# Top.net
KiCad netlist of a schematic drawn in Altium Designer
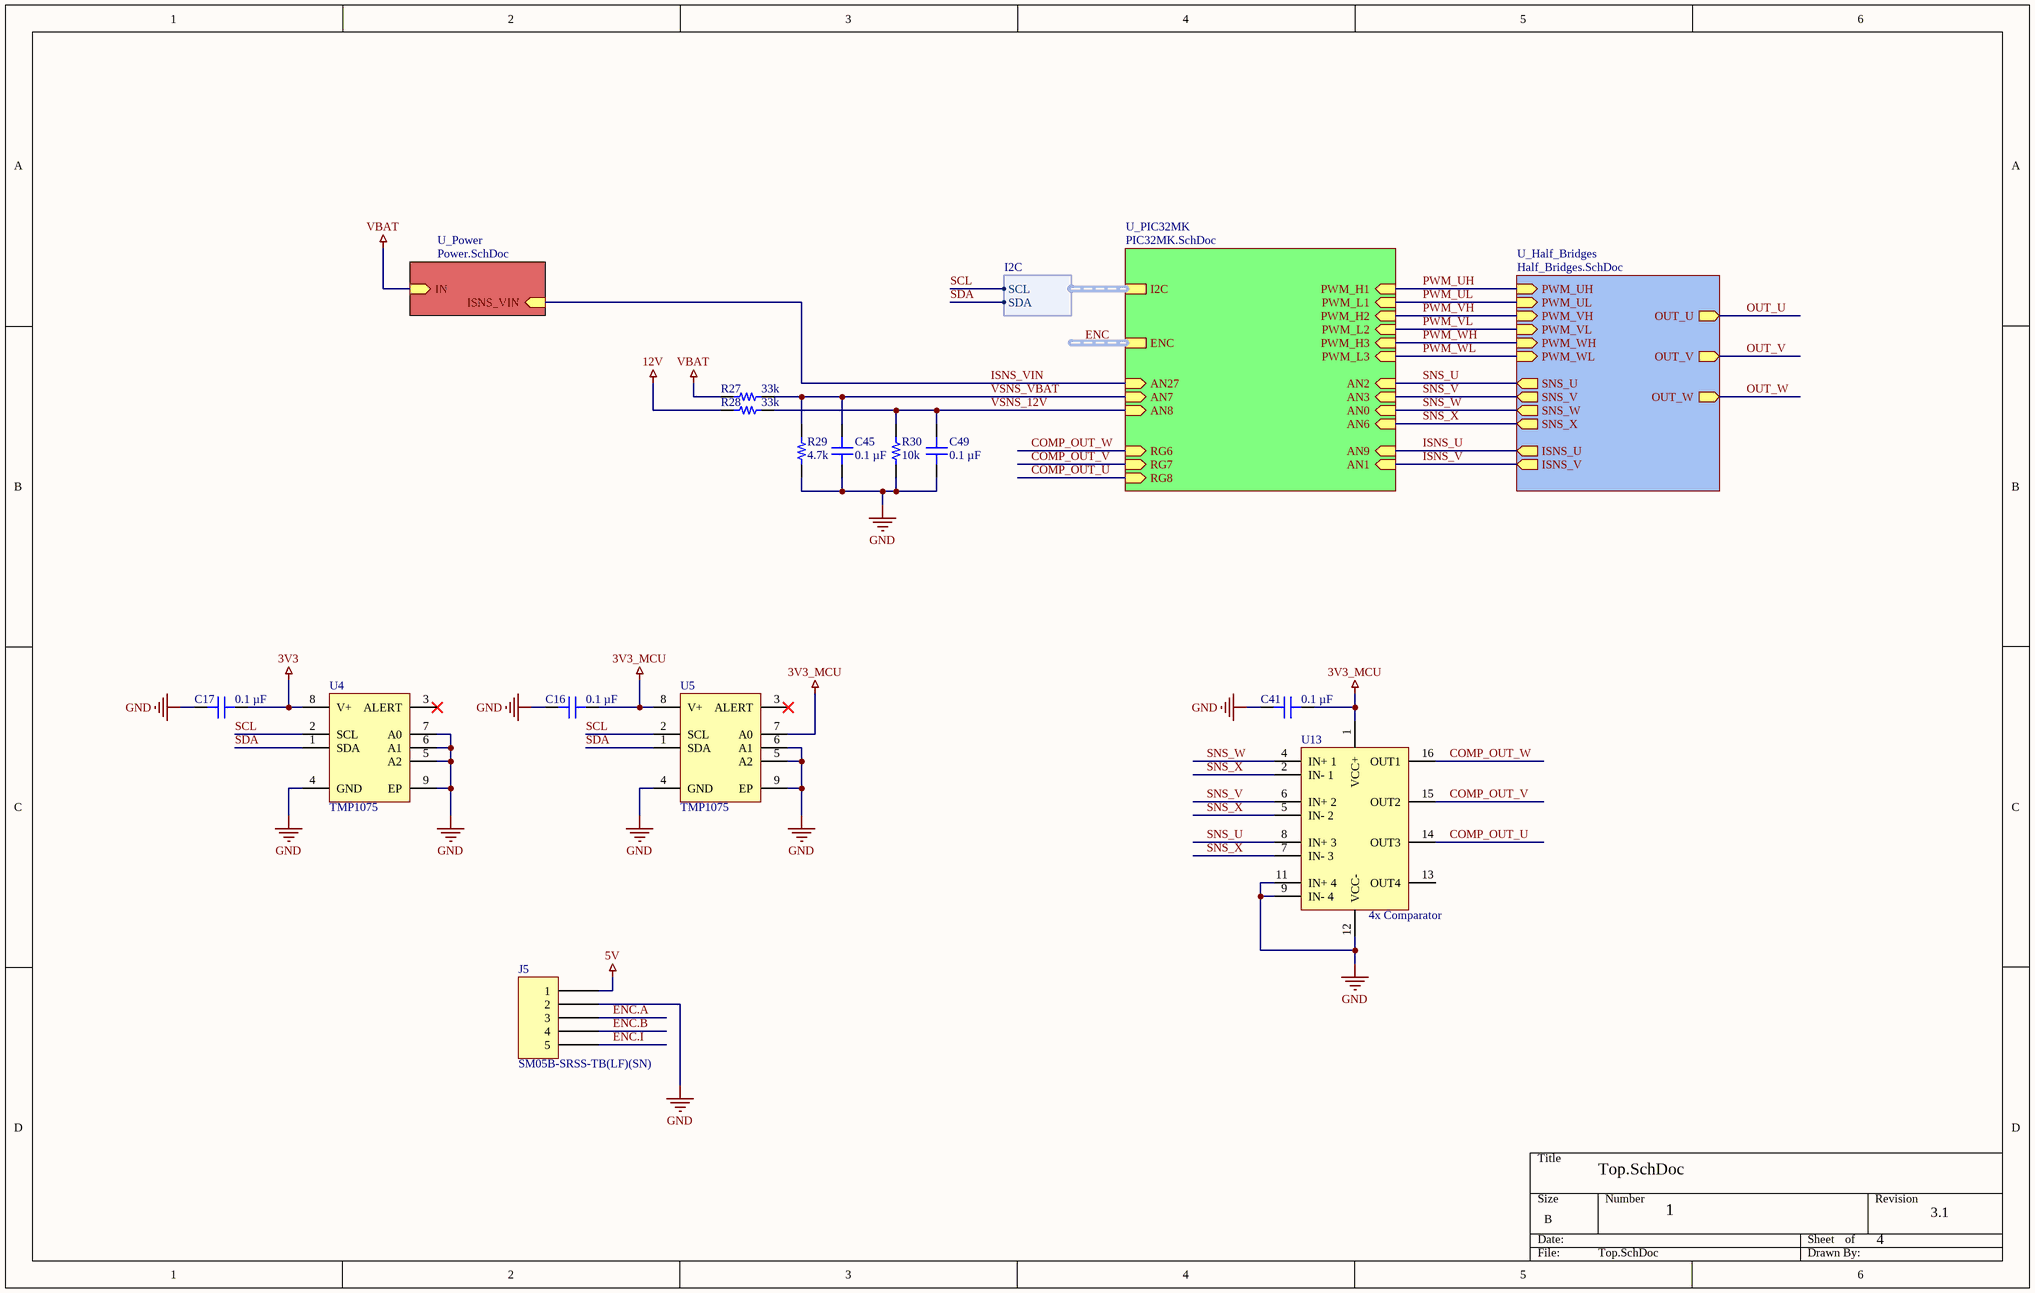
[diagram p0: Top.SchDoc]

(export (version "E")
  (design (tool "Eeschema 10.0.6"))
  (components
    (comp (ref "C16")
      (value "0.1 µF")
      (footprint "CAP 0402_1005")
      (description "CAP CER 0.1UF 16V X7R 0402")
      (fields (field (name "PART NUMBER") "C0402C104K4RACAUTO") (field (name "MANUFACTURER") "KEMET"))
      (libsource (lib "Celestial Altium Library - altium_library") (part "Capacitor"))
    )
    (comp (ref "C17")
      (value "0.1 µF")
      (footprint "CAP 0402_1005")
      (description "CAP CER 0.1UF 16V X7R 0402")
      (fields (field (name "PART NUMBER") "C0402C104K4RACAUTO") (field (name "MANUFACTURER") "KEMET"))
      (libsource (lib "Celestial Altium Library - altium_library") (part "Capacitor"))
    )
    (comp (ref "C41")
      (value "0.1 µF")
      (footprint "CAP 0402_1005")
      (description "CAP CER 0.1UF 16V X7R 0402")
      (fields (field (name "PART NUMBER") "C0402C104K4RACAUTO") (field (name "MANUFACTURER") "KEMET"))
      (libsource (lib "Celestial Altium Library - altium_library") (part "Capacitor"))
    )
    (comp (ref "C45")
      (value "0.1 µF")
      (footprint "CAP 0402_1005")
      (description "CAP CER 0.1UF 16V X7R 0402")
      (fields (field (name "PART NUMBER") "C0402C104K4RACAUTO") (field (name "MANUFACTURER") "KEMET"))
      (libsource (lib "Celestial Altium Library - altium_library") (part "Capacitor"))
    )
    (comp (ref "C49")
      (value "0.1 µF")
      (footprint "CAP 0402_1005")
      (description "CAP CER 0.1UF 16V X7R 0402")
      (fields (field (name "PART NUMBER") "C0402C104K4RACAUTO") (field (name "MANUFACTURER") "KEMET"))
      (libsource (lib "Celestial Altium Library - altium_library") (part "Capacitor"))
    )
    (comp (ref "J5")
      (value "SM05B-SRSS-TB(LF)(SN)")
      (footprint "JST SM05B-SRSS-TB")
      (description "CONN HEADER SMD R/A 5POS 1MM")
      (fields (field (name "MANUFACTURER") "JST Sales America Inc."))
      (libsource (lib "Celestial Altium Library - altium_library") (part "5 Pin"))
    )
    (comp (ref "R27")
      (value "33k")
      (footprint "RES 0402_1005")
      (description "RES 14.3K OHM 1% 1/10W 0402")
      (fields
        (field (name "PART NUMBER") "RK73H1ETTP1432F")
        (field (name "MANUFACTURER") "KOA Speer Electronics, Inc.")
      )
      (libsource (lib "Celestial Altium Library - altium_library") (part "Resistor"))
    )
    (comp (ref "R28")
      (value "33k")
      (footprint "RES 0402_1005")
      (description "RES 14.3K OHM 1% 1/10W 0402")
      (fields
        (field (name "PART NUMBER") "RK73H1ETTP1432F")
        (field (name "MANUFACTURER") "KOA Speer Electronics, Inc.")
      )
      (libsource (lib "Celestial Altium Library - altium_library") (part "Resistor"))
    )
    (comp (ref "R29")
      (value "4.7k")
      (footprint "RES 0402_1005")
      (description "RES 14.3K OHM 1% 1/10W 0402")
      (fields
        (field (name "PART NUMBER") "RK73H1ETTP1432F")
        (field (name "MANUFACTURER") "KOA Speer Electronics, Inc.")
      )
      (libsource (lib "Celestial Altium Library - altium_library") (part "Resistor"))
    )
    (comp (ref "R30")
      (value "10k")
      (footprint "RES 0402_1005")
      (description "RES 14.3K OHM 1% 1/10W 0402")
      (fields
        (field (name "PART NUMBER") "RK73H1ETTP1432F")
        (field (name "MANUFACTURER") "KOA Speer Electronics, Inc.")
      )
      (libsource (lib "Celestial Altium Library - altium_library") (part "Resistor"))
    )
    (comp (ref "U4")
      (value "TMP1075")
      (footprint "8_WSON_2x2_0.5mm")
      (description "I2C TEMP SENSOR")
      (libsource (lib "IC") (part "TMP1075"))
    )
    (comp (ref "U5")
      (value "TMP1075")
      (footprint "8_WSON_2x2_0.5mm")
      (description "I2C TEMP SENSOR")
      (libsource (lib "IC") (part "TMP1075"))
    )
    (comp (ref "U13")
      (value "4x Comparator")
      (footprint "QFN50P300X300X100-16N")
      (description "Comparator General Purpose CMOS, DTL, MOS, Open-Collector, TTL 16-QFN (3x3)")
      (libsource (lib "IC") (part "LM2901Q4T"))
    )
  )
  (nets
    (net (code "3") (name "/COMP_OUT_U") (class "Default")
      (node (ref "U13") (pin "14") (pinfunction "OUT3_14") (pintype "passive"))
    )
    (net (code "4") (name "/COMP_OUT_V") (class "Default")
      (node (ref "U13") (pin "15") (pinfunction "OUT2_15") (pintype "passive"))
    )
    (net (code "5") (name "/COMP_OUT_W") (class "Default")
      (node (ref "U13") (pin "16") (pinfunction "OUT1_16") (pintype "passive"))
    )
    (net (code "6") (name "/ENC.A") (class "Default")
      (node (ref "J5") (pin "3") (pinfunction "3_3") (pintype "passive"))
    )
    (net (code "7") (name "/ENC.B") (class "Default")
      (node (ref "J5") (pin "4") (pinfunction "4_4") (pintype "passive"))
    )
    (net (code "8") (name "/ENC.I") (class "Default")
      (node (ref "J5") (pin "5") (pinfunction "5_5") (pintype "passive"))
    )
    (net (code "21") (name "/SCL") (class "Default")
      (node (ref "U4") (pin "2") (pinfunction "SCL_2") (pintype "passive"))
      (node (ref "U5") (pin "2") (pinfunction "SCL_2") (pintype "passive"))
    )
    (net (code "22") (name "/SDA") (class "Default")
      (node (ref "U4") (pin "1") (pinfunction "SDA_1") (pintype "passive"))
      (node (ref "U5") (pin "1") (pinfunction "SDA_1") (pintype "passive"))
    )
    (net (code "23") (name "/SNS_U") (class "Default")
      (node (ref "U13") (pin "8") (pinfunction "IN+_3_8") (pintype "passive"))
    )
    (net (code "24") (name "/SNS_V") (class "Default")
      (node (ref "U13") (pin "6") (pinfunction "IN+_2_6") (pintype "passive"))
    )
    (net (code "25") (name "/SNS_W") (class "Default")
      (node (ref "U13") (pin "4") (pinfunction "IN+_1_4") (pintype "passive"))
    )
    (net (code "26") (name "/SNS_X") (class "Default")
      (node (ref "U13") (pin "2") (pinfunction "IN-_1_2") (pintype "passive"))
      (node (ref "U13") (pin "5") (pinfunction "IN-_2_5") (pintype "passive"))
      (node (ref "U13") (pin "7") (pinfunction "IN-_3_7") (pintype "passive"))
    )
    (net (code "27") (name "/VSNS_12V") (class "Default")
      (node (ref "C49") (pin "2") (pinfunction "2_2") (pintype "passive"))
      (node (ref "R28") (pin "1") (pinfunction "1_1") (pintype "passive"))
      (node (ref "R30") (pin "1") (pinfunction "1_1") (pintype "passive"))
    )
    (net (code "28") (name "/VSNS_VBAT") (class "Default")
      (node (ref "C45") (pin "2") (pinfunction "2_2") (pintype "passive"))
      (node (ref "R27") (pin "1") (pinfunction "1_1") (pintype "passive"))
      (node (ref "R29") (pin "1") (pinfunction "1_1") (pintype "passive"))
    )
    (net (code "31") (name "3V3") (class "Default")
      (node (ref "C17") (pin "2") (pinfunction "2_2") (pintype "passive"))
      (node (ref "U4") (pin "8") (pinfunction "V+_8") (pintype "passive"))
    )
    (net (code "32") (name "3V3_MCU") (class "Default")
      (node (ref "C16") (pin "2") (pinfunction "2_2") (pintype "passive"))
      (node (ref "C41") (pin "2") (pinfunction "2_2") (pintype "passive"))
      (node (ref "U13") (pin "1") (pinfunction "VCC+_1") (pintype "passive"))
      (node (ref "U5") (pin "7") (pinfunction "A0_7") (pintype "passive"))
      (node (ref "U5") (pin "8") (pinfunction "V+_8") (pintype "passive"))
    )
    (net (code "33") (name "5V") (class "Default")
      (node (ref "J5") (pin "1") (pinfunction "1_1") (pintype "passive"))
    )
    (net (code "34") (name "12V") (class "Default")
      (node (ref "R28") (pin "2") (pinfunction "2_2") (pintype "passive"))
    )
    (net (code "35") (name "GND") (class "Default")
      (node (ref "C16") (pin "1") (pinfunction "1_1") (pintype "passive"))
      (node (ref "C17") (pin "1") (pinfunction "1_1") (pintype "passive"))
      (node (ref "C41") (pin "1") (pinfunction "1_1") (pintype "passive"))
      (node (ref "C45") (pin "1") (pinfunction "1_1") (pintype "passive"))
      (node (ref "C49") (pin "1") (pinfunction "1_1") (pintype "passive"))
      (node (ref "J5") (pin "2") (pinfunction "2_2") (pintype "passive"))
      (node (ref "R29") (pin "2") (pinfunction "2_2") (pintype "passive"))
      (node (ref "R30") (pin "2") (pinfunction "2_2") (pintype "passive"))
      (node (ref "U13") (pin "11") (pinfunction "IN+_4_11") (pintype "passive"))
      (node (ref "U13") (pin "12") (pinfunction "VCC-_12") (pintype "passive"))
      (node (ref "U13") (pin "9") (pinfunction "IN-_4_9") (pintype "passive"))
      (node (ref "U4") (pin "4") (pinfunction "GND_4") (pintype "passive"))
      (node (ref "U4") (pin "5") (pinfunction "A2_5") (pintype "passive"))
      (node (ref "U4") (pin "6") (pinfunction "A1_6") (pintype "passive"))
      (node (ref "U4") (pin "7") (pinfunction "A0_7") (pintype "passive"))
      (node (ref "U4") (pin "9") (pinfunction "EP_9") (pintype "passive"))
      (node (ref "U5") (pin "4") (pinfunction "GND_4") (pintype "passive"))
      (node (ref "U5") (pin "5") (pinfunction "A2_5") (pintype "passive"))
      (node (ref "U5") (pin "6") (pinfunction "A1_6") (pintype "passive"))
      (node (ref "U5") (pin "9") (pinfunction "EP_9") (pintype "passive"))
    )
    (net (code "36") (name "VBAT") (class "Default")
      (node (ref "R27") (pin "2") (pinfunction "2_2") (pintype "passive"))
    )
    (net (code "37") (name "unconnected-(U4-ALERT-Pad3)") (class "Default")
      (node (ref "U4") (pin "3") (pinfunction "ALERT_3") (pintype "passive+no_connect"))
    )
    (net (code "38") (name "unconnected-(U5-ALERT-Pad3)") (class "Default")
      (node (ref "U5") (pin "3") (pinfunction "ALERT_3") (pintype "passive+no_connect"))
    )
    (net (code "39") (name "unconnected-(U13-OUT4-Pad13)") (class "Default")
      (node (ref "U13") (pin "13") (pinfunction "OUT4_13") (pintype "passive"))
    )
  )
)
